# LED-Cube-Schematic.net
KiCad netlist of a schematic drawn in EAGLE
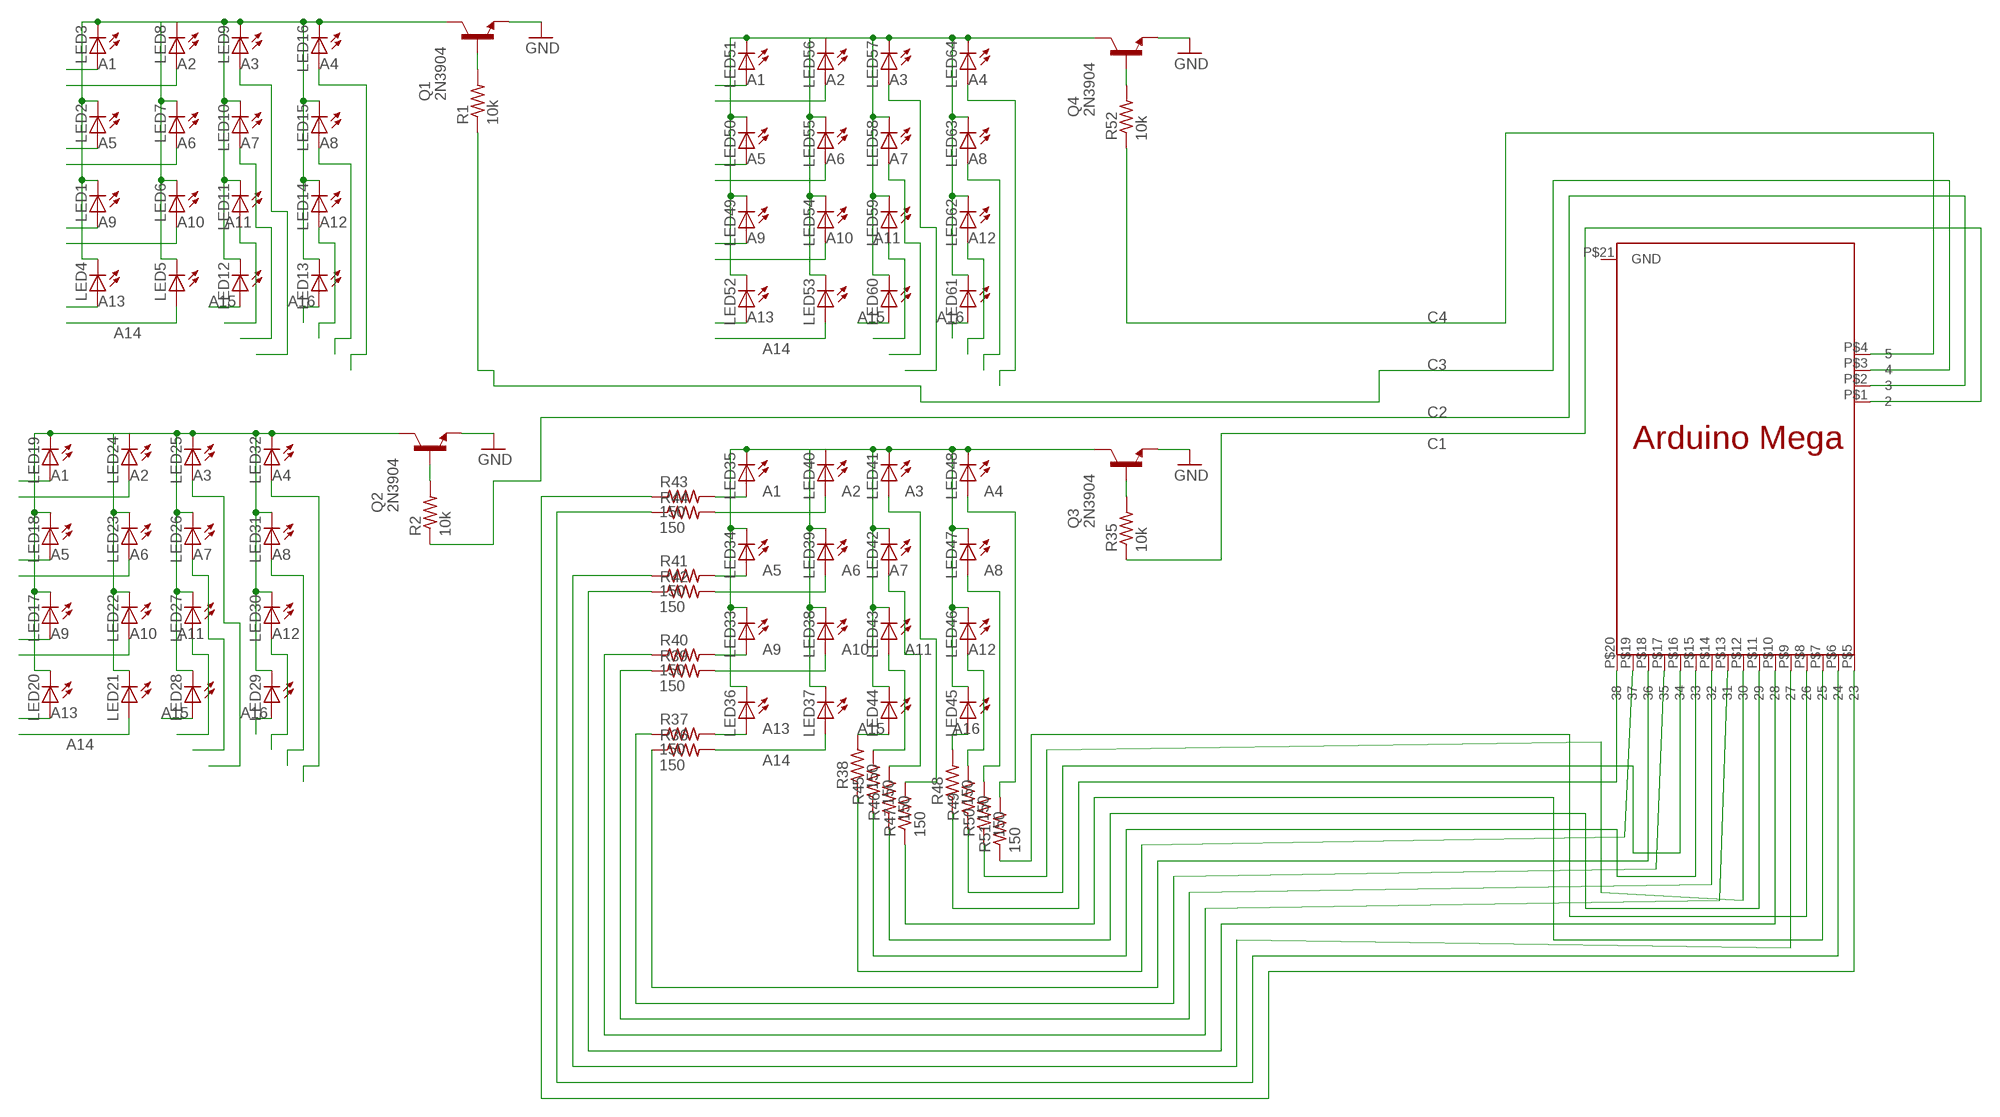
[diagram p0: schematic, sheet 1]

(export (version "E")
  (design (tool "Eeschema 10.0.6"))
  (components
    (comp (ref "LED1")
      (value "LED3MM")
      (footprint "eagle-import:LED3MM")
      (libsource (lib "eagle-import") (part "LED3MM"))
    )
    (comp (ref "LED2")
      (value "LED3MM")
      (footprint "eagle-import:LED3MM")
      (libsource (lib "eagle-import") (part "LED3MM"))
    )
    (comp (ref "LED3")
      (value "LED3MM")
      (footprint "eagle-import:LED3MM")
      (libsource (lib "eagle-import") (part "LED3MM"))
    )
    (comp (ref "LED4")
      (value "LED3MM")
      (footprint "eagle-import:LED3MM")
      (libsource (lib "eagle-import") (part "LED3MM"))
    )
    (comp (ref "LED5")
      (value "LED3MM")
      (footprint "eagle-import:LED3MM")
      (libsource (lib "eagle-import") (part "LED3MM"))
    )
    (comp (ref "LED6")
      (value "LED3MM")
      (footprint "eagle-import:LED3MM")
      (libsource (lib "eagle-import") (part "LED3MM"))
    )
    (comp (ref "LED7")
      (value "LED3MM")
      (footprint "eagle-import:LED3MM")
      (libsource (lib "eagle-import") (part "LED3MM"))
    )
    (comp (ref "LED8")
      (value "LED3MM")
      (footprint "eagle-import:LED3MM")
      (libsource (lib "eagle-import") (part "LED3MM"))
    )
    (comp (ref "LED9")
      (value "LED3MM")
      (footprint "eagle-import:LED3MM")
      (libsource (lib "eagle-import") (part "LED3MM"))
    )
    (comp (ref "LED10")
      (value "LED3MM")
      (footprint "eagle-import:LED3MM")
      (libsource (lib "eagle-import") (part "LED3MM"))
    )
    (comp (ref "LED11")
      (value "LED3MM")
      (footprint "eagle-import:LED3MM")
      (libsource (lib "eagle-import") (part "LED3MM"))
    )
    (comp (ref "LED12")
      (value "LED3MM")
      (footprint "eagle-import:LED3MM")
      (libsource (lib "eagle-import") (part "LED3MM"))
    )
    (comp (ref "LED13")
      (value "LED3MM")
      (footprint "eagle-import:LED3MM")
      (libsource (lib "eagle-import") (part "LED3MM"))
    )
    (comp (ref "LED14")
      (value "LED3MM")
      (footprint "eagle-import:LED3MM")
      (libsource (lib "eagle-import") (part "LED3MM"))
    )
    (comp (ref "LED15")
      (value "LED3MM")
      (footprint "eagle-import:LED3MM")
      (libsource (lib "eagle-import") (part "LED3MM"))
    )
    (comp (ref "LED16")
      (value "LED3MM")
      (footprint "eagle-import:LED3MM")
      (libsource (lib "eagle-import") (part "LED3MM"))
    )
    (comp (ref "LED17")
      (value "LED3MM")
      (footprint "eagle-import:LED3MM")
      (libsource (lib "eagle-import") (part "LED3MM"))
    )
    (comp (ref "LED18")
      (value "LED3MM")
      (footprint "eagle-import:LED3MM")
      (libsource (lib "eagle-import") (part "LED3MM"))
    )
    (comp (ref "LED19")
      (value "LED3MM")
      (footprint "eagle-import:LED3MM")
      (libsource (lib "eagle-import") (part "LED3MM"))
    )
    (comp (ref "LED20")
      (value "LED3MM")
      (footprint "eagle-import:LED3MM")
      (libsource (lib "eagle-import") (part "LED3MM"))
    )
    (comp (ref "LED21")
      (value "LED3MM")
      (footprint "eagle-import:LED3MM")
      (libsource (lib "eagle-import") (part "LED3MM"))
    )
    (comp (ref "LED22")
      (value "LED3MM")
      (footprint "eagle-import:LED3MM")
      (libsource (lib "eagle-import") (part "LED3MM"))
    )
    (comp (ref "LED23")
      (value "LED3MM")
      (footprint "eagle-import:LED3MM")
      (libsource (lib "eagle-import") (part "LED3MM"))
    )
    (comp (ref "LED24")
      (value "LED3MM")
      (footprint "eagle-import:LED3MM")
      (libsource (lib "eagle-import") (part "LED3MM"))
    )
    (comp (ref "LED25")
      (value "LED3MM")
      (footprint "eagle-import:LED3MM")
      (libsource (lib "eagle-import") (part "LED3MM"))
    )
    (comp (ref "LED26")
      (value "LED3MM")
      (footprint "eagle-import:LED3MM")
      (libsource (lib "eagle-import") (part "LED3MM"))
    )
    (comp (ref "LED27")
      (value "LED3MM")
      (footprint "eagle-import:LED3MM")
      (libsource (lib "eagle-import") (part "LED3MM"))
    )
    (comp (ref "LED28")
      (value "LED3MM")
      (footprint "eagle-import:LED3MM")
      (libsource (lib "eagle-import") (part "LED3MM"))
    )
    (comp (ref "LED29")
      (value "LED3MM")
      (footprint "eagle-import:LED3MM")
      (libsource (lib "eagle-import") (part "LED3MM"))
    )
    (comp (ref "LED30")
      (value "LED3MM")
      (footprint "eagle-import:LED3MM")
      (libsource (lib "eagle-import") (part "LED3MM"))
    )
    (comp (ref "LED31")
      (value "LED3MM")
      (footprint "eagle-import:LED3MM")
      (libsource (lib "eagle-import") (part "LED3MM"))
    )
    (comp (ref "LED32")
      (value "LED3MM")
      (footprint "eagle-import:LED3MM")
      (libsource (lib "eagle-import") (part "LED3MM"))
    )
    (comp (ref "LED33")
      (value "LED3MM")
      (footprint "eagle-import:LED3MM")
      (libsource (lib "eagle-import") (part "LED3MM"))
    )
    (comp (ref "LED34")
      (value "LED3MM")
      (footprint "eagle-import:LED3MM")
      (libsource (lib "eagle-import") (part "LED3MM"))
    )
    (comp (ref "LED35")
      (value "LED3MM")
      (footprint "eagle-import:LED3MM")
      (libsource (lib "eagle-import") (part "LED3MM"))
    )
    (comp (ref "LED36")
      (value "LED3MM")
      (footprint "eagle-import:LED3MM")
      (libsource (lib "eagle-import") (part "LED3MM"))
    )
    (comp (ref "LED37")
      (value "LED3MM")
      (footprint "eagle-import:LED3MM")
      (libsource (lib "eagle-import") (part "LED3MM"))
    )
    (comp (ref "LED38")
      (value "LED3MM")
      (footprint "eagle-import:LED3MM")
      (libsource (lib "eagle-import") (part "LED3MM"))
    )
    (comp (ref "LED39")
      (value "LED3MM")
      (footprint "eagle-import:LED3MM")
      (libsource (lib "eagle-import") (part "LED3MM"))
    )
    (comp (ref "LED40")
      (value "LED3MM")
      (footprint "eagle-import:LED3MM")
      (libsource (lib "eagle-import") (part "LED3MM"))
    )
    (comp (ref "LED41")
      (value "LED3MM")
      (footprint "eagle-import:LED3MM")
      (libsource (lib "eagle-import") (part "LED3MM"))
    )
    (comp (ref "LED42")
      (value "LED3MM")
      (footprint "eagle-import:LED3MM")
      (libsource (lib "eagle-import") (part "LED3MM"))
    )
    (comp (ref "LED43")
      (value "LED3MM")
      (footprint "eagle-import:LED3MM")
      (libsource (lib "eagle-import") (part "LED3MM"))
    )
    (comp (ref "LED44")
      (value "LED3MM")
      (footprint "eagle-import:LED3MM")
      (libsource (lib "eagle-import") (part "LED3MM"))
    )
    (comp (ref "LED45")
      (value "LED3MM")
      (footprint "eagle-import:LED3MM")
      (libsource (lib "eagle-import") (part "LED3MM"))
    )
    (comp (ref "LED46")
      (value "LED3MM")
      (footprint "eagle-import:LED3MM")
      (libsource (lib "eagle-import") (part "LED3MM"))
    )
    (comp (ref "LED47")
      (value "LED3MM")
      (footprint "eagle-import:LED3MM")
      (libsource (lib "eagle-import") (part "LED3MM"))
    )
    (comp (ref "LED48")
      (value "LED3MM")
      (footprint "eagle-import:LED3MM")
      (libsource (lib "eagle-import") (part "LED3MM"))
    )
    (comp (ref "LED49")
      (value "LED3MM")
      (footprint "eagle-import:LED3MM")
      (libsource (lib "eagle-import") (part "LED3MM"))
    )
    (comp (ref "LED50")
      (value "LED3MM")
      (footprint "eagle-import:LED3MM")
      (libsource (lib "eagle-import") (part "LED3MM"))
    )
    (comp (ref "LED51")
      (value "LED3MM")
      (footprint "eagle-import:LED3MM")
      (libsource (lib "eagle-import") (part "LED3MM"))
    )
    (comp (ref "LED52")
      (value "LED3MM")
      (footprint "eagle-import:LED3MM")
      (libsource (lib "eagle-import") (part "LED3MM"))
    )
    (comp (ref "LED53")
      (value "LED3MM")
      (footprint "eagle-import:LED3MM")
      (libsource (lib "eagle-import") (part "LED3MM"))
    )
    (comp (ref "LED54")
      (value "LED3MM")
      (footprint "eagle-import:LED3MM")
      (libsource (lib "eagle-import") (part "LED3MM"))
    )
    (comp (ref "LED55")
      (value "LED3MM")
      (footprint "eagle-import:LED3MM")
      (libsource (lib "eagle-import") (part "LED3MM"))
    )
    (comp (ref "LED56")
      (value "LED3MM")
      (footprint "eagle-import:LED3MM")
      (libsource (lib "eagle-import") (part "LED3MM"))
    )
    (comp (ref "LED57")
      (value "LED3MM")
      (footprint "eagle-import:LED3MM")
      (libsource (lib "eagle-import") (part "LED3MM"))
    )
    (comp (ref "LED58")
      (value "LED3MM")
      (footprint "eagle-import:LED3MM")
      (libsource (lib "eagle-import") (part "LED3MM"))
    )
    (comp (ref "LED59")
      (value "LED3MM")
      (footprint "eagle-import:LED3MM")
      (libsource (lib "eagle-import") (part "LED3MM"))
    )
    (comp (ref "LED60")
      (value "LED3MM")
      (footprint "eagle-import:LED3MM")
      (libsource (lib "eagle-import") (part "LED3MM"))
    )
    (comp (ref "LED61")
      (value "LED3MM")
      (footprint "eagle-import:LED3MM")
      (libsource (lib "eagle-import") (part "LED3MM"))
    )
    (comp (ref "LED62")
      (value "LED3MM")
      (footprint "eagle-import:LED3MM")
      (libsource (lib "eagle-import") (part "LED3MM"))
    )
    (comp (ref "LED63")
      (value "LED3MM")
      (footprint "eagle-import:LED3MM")
      (libsource (lib "eagle-import") (part "LED3MM"))
    )
    (comp (ref "LED64")
      (value "LED3MM")
      (footprint "eagle-import:LED3MM")
      (libsource (lib "eagle-import") (part "LED3MM"))
    )
    (comp (ref "Q1")
      (value "2N3904")
      (footprint "eagle-import:TO92")
      (libsource (lib "eagle-import") (part "2N3904"))
    )
    (comp (ref "Q2")
      (value "2N3904")
      (footprint "eagle-import:TO92")
      (libsource (lib "eagle-import") (part "2N3904"))
    )
    (comp (ref "Q3")
      (value "2N3904")
      (footprint "eagle-import:TO92")
      (libsource (lib "eagle-import") (part "2N3904"))
    )
    (comp (ref "Q4")
      (value "2N3904")
      (footprint "eagle-import:TO92")
      (libsource (lib "eagle-import") (part "2N3904"))
    )
    (comp (ref "R1")
      (value "10k")
      (footprint "eagle-import:0207_7")
      (libsource (lib "eagle-import") (part "R-US_0207/7"))
    )
    (comp (ref "R2")
      (value "10k")
      (footprint "eagle-import:0207_7")
      (libsource (lib "eagle-import") (part "R-US_0207/7"))
    )
    (comp (ref "R35")
      (value "10k")
      (footprint "eagle-import:0207_7")
      (libsource (lib "eagle-import") (part "R-US_0207/7"))
    )
    (comp (ref "R36")
      (value "150")
      (footprint "eagle-import:0207_7")
      (libsource (lib "eagle-import") (part "R-US_0207/7"))
    )
    (comp (ref "R37")
      (value "150")
      (footprint "eagle-import:0207_7")
      (libsource (lib "eagle-import") (part "R-US_0207/7"))
    )
    (comp (ref "R38")
      (value "150")
      (footprint "eagle-import:0207_7")
      (libsource (lib "eagle-import") (part "R-US_0207/7"))
    )
    (comp (ref "R39")
      (value "150")
      (footprint "eagle-import:0207_7")
      (libsource (lib "eagle-import") (part "R-US_0207/7"))
    )
    (comp (ref "R40")
      (value "150")
      (footprint "eagle-import:0207_7")
      (libsource (lib "eagle-import") (part "R-US_0207/7"))
    )
    (comp (ref "R41")
      (value "150")
      (footprint "eagle-import:0207_7")
      (libsource (lib "eagle-import") (part "R-US_0207/7"))
    )
    (comp (ref "R42")
      (value "150")
      (footprint "eagle-import:0207_7")
      (libsource (lib "eagle-import") (part "R-US_0207/7"))
    )
    (comp (ref "R43")
      (value "150")
      (footprint "eagle-import:0207_7")
      (libsource (lib "eagle-import") (part "R-US_0207/7"))
    )
    (comp (ref "R44")
      (value "150")
      (footprint "eagle-import:0207_7")
      (libsource (lib "eagle-import") (part "R-US_0207/7"))
    )
    (comp (ref "R45")
      (value "150")
      (footprint "eagle-import:0207_7")
      (libsource (lib "eagle-import") (part "R-US_0207/7"))
    )
    (comp (ref "R46")
      (value "150")
      (footprint "eagle-import:0207_7")
      (libsource (lib "eagle-import") (part "R-US_0207/7"))
    )
    (comp (ref "R47")
      (value "150")
      (footprint "eagle-import:0207_7")
      (libsource (lib "eagle-import") (part "R-US_0207/7"))
    )
    (comp (ref "R48")
      (value "150")
      (footprint "eagle-import:0207_7")
      (libsource (lib "eagle-import") (part "R-US_0207/7"))
    )
    (comp (ref "R49")
      (value "150")
      (footprint "eagle-import:0207_7")
      (libsource (lib "eagle-import") (part "R-US_0207/7"))
    )
    (comp (ref "R50")
      (value "150")
      (footprint "eagle-import:0207_7")
      (libsource (lib "eagle-import") (part "R-US_0207/7"))
    )
    (comp (ref "R51")
      (value "150")
      (footprint "eagle-import:0207_7")
      (libsource (lib "eagle-import") (part "R-US_0207/7"))
    )
    (comp (ref "R52")
      (value "10k")
      (footprint "eagle-import:0207_7")
      (libsource (lib "eagle-import") (part "R-US_0207/7"))
    )
    (comp (ref "U$1")
      (value "MEGA")
      (footprint "eagle-import:MEGAPACKAGE")
      (libsource (lib "eagle-import") (part "MEGA"))
    )
  )
  (nets
    (net (code "1") (name "/A1") (class "Default")
      (node (ref "LED19") (pin "A") (pinfunction "A_A") (pintype "passive"))
      (node (ref "LED3") (pin "A") (pinfunction "A_A") (pintype "passive"))
      (node (ref "LED35") (pin "A") (pinfunction "A_A") (pintype "passive"))
      (node (ref "LED51") (pin "A") (pinfunction "A_A") (pintype "passive"))
      (node (ref "R43") (pin "2") (pinfunction "2_2") (pintype "passive"))
    )
    (net (code "2") (name "/A2") (class "Default")
      (node (ref "LED24") (pin "A") (pinfunction "A_A") (pintype "passive"))
      (node (ref "LED40") (pin "A") (pinfunction "A_A") (pintype "passive"))
      (node (ref "LED56") (pin "A") (pinfunction "A_A") (pintype "passive"))
      (node (ref "LED8") (pin "A") (pinfunction "A_A") (pintype "passive"))
      (node (ref "R44") (pin "2") (pinfunction "2_2") (pintype "passive"))
    )
    (net (code "3") (name "/A3") (class "Default")
      (node (ref "LED25") (pin "A") (pinfunction "A_A") (pintype "passive"))
      (node (ref "LED41") (pin "A") (pinfunction "A_A") (pintype "passive"))
      (node (ref "LED57") (pin "A") (pinfunction "A_A") (pintype "passive"))
      (node (ref "LED9") (pin "A") (pinfunction "A_A") (pintype "passive"))
      (node (ref "R47") (pin "2") (pinfunction "2_2") (pintype "passive"))
    )
    (net (code "4") (name "/A4") (class "Default")
      (node (ref "LED16") (pin "A") (pinfunction "A_A") (pintype "passive"))
      (node (ref "LED32") (pin "A") (pinfunction "A_A") (pintype "passive"))
      (node (ref "LED48") (pin "A") (pinfunction "A_A") (pintype "passive"))
      (node (ref "LED64") (pin "A") (pinfunction "A_A") (pintype "passive"))
      (node (ref "R51") (pin "2") (pinfunction "2_2") (pintype "passive"))
    )
    (net (code "5") (name "/A5") (class "Default")
      (node (ref "LED18") (pin "A") (pinfunction "A_A") (pintype "passive"))
      (node (ref "LED2") (pin "A") (pinfunction "A_A") (pintype "passive"))
      (node (ref "LED34") (pin "A") (pinfunction "A_A") (pintype "passive"))
      (node (ref "LED50") (pin "A") (pinfunction "A_A") (pintype "passive"))
      (node (ref "R41") (pin "2") (pinfunction "2_2") (pintype "passive"))
    )
    (net (code "6") (name "/A6") (class "Default")
      (node (ref "LED23") (pin "A") (pinfunction "A_A") (pintype "passive"))
      (node (ref "LED39") (pin "A") (pinfunction "A_A") (pintype "passive"))
      (node (ref "LED55") (pin "A") (pinfunction "A_A") (pintype "passive"))
      (node (ref "LED7") (pin "A") (pinfunction "A_A") (pintype "passive"))
      (node (ref "R42") (pin "2") (pinfunction "2_2") (pintype "passive"))
    )
    (net (code "7") (name "/A7") (class "Default")
      (node (ref "LED10") (pin "A") (pinfunction "A_A") (pintype "passive"))
      (node (ref "LED26") (pin "A") (pinfunction "A_A") (pintype "passive"))
      (node (ref "LED42") (pin "A") (pinfunction "A_A") (pintype "passive"))
      (node (ref "LED58") (pin "A") (pinfunction "A_A") (pintype "passive"))
      (node (ref "R46") (pin "2") (pinfunction "2_2") (pintype "passive"))
    )
    (net (code "8") (name "/A8") (class "Default")
      (node (ref "LED15") (pin "A") (pinfunction "A_A") (pintype "passive"))
      (node (ref "LED31") (pin "A") (pinfunction "A_A") (pintype "passive"))
      (node (ref "LED47") (pin "A") (pinfunction "A_A") (pintype "passive"))
      (node (ref "LED63") (pin "A") (pinfunction "A_A") (pintype "passive"))
      (node (ref "R50") (pin "2") (pinfunction "2_2") (pintype "passive"))
    )
    (net (code "9") (name "/A9") (class "Default")
      (node (ref "LED1") (pin "A") (pinfunction "A_A") (pintype "passive"))
      (node (ref "LED17") (pin "A") (pinfunction "A_A") (pintype "passive"))
      (node (ref "LED33") (pin "A") (pinfunction "A_A") (pintype "passive"))
      (node (ref "LED49") (pin "A") (pinfunction "A_A") (pintype "passive"))
      (node (ref "R40") (pin "2") (pinfunction "2_2") (pintype "passive"))
    )
    (net (code "10") (name "/A10") (class "Default")
      (node (ref "LED22") (pin "A") (pinfunction "A_A") (pintype "passive"))
      (node (ref "LED38") (pin "A") (pinfunction "A_A") (pintype "passive"))
      (node (ref "LED54") (pin "A") (pinfunction "A_A") (pintype "passive"))
      (node (ref "LED6") (pin "A") (pinfunction "A_A") (pintype "passive"))
      (node (ref "R39") (pin "2") (pinfunction "2_2") (pintype "passive"))
    )
    (net (code "11") (name "/A11") (class "Default")
      (node (ref "LED11") (pin "A") (pinfunction "A_A") (pintype "passive"))
      (node (ref "LED27") (pin "A") (pinfunction "A_A") (pintype "passive"))
      (node (ref "LED43") (pin "A") (pinfunction "A_A") (pintype "passive"))
      (node (ref "LED59") (pin "A") (pinfunction "A_A") (pintype "passive"))
      (node (ref "R45") (pin "2") (pinfunction "2_2") (pintype "passive"))
    )
    (net (code "12") (name "/A12") (class "Default")
      (node (ref "LED14") (pin "A") (pinfunction "A_A") (pintype "passive"))
      (node (ref "LED30") (pin "A") (pinfunction "A_A") (pintype "passive"))
      (node (ref "LED46") (pin "A") (pinfunction "A_A") (pintype "passive"))
      (node (ref "LED62") (pin "A") (pinfunction "A_A") (pintype "passive"))
      (node (ref "R49") (pin "2") (pinfunction "2_2") (pintype "passive"))
    )
    (net (code "13") (name "/A13") (class "Default")
      (node (ref "LED20") (pin "A") (pinfunction "A_A") (pintype "passive"))
      (node (ref "LED36") (pin "A") (pinfunction "A_A") (pintype "passive"))
      (node (ref "LED4") (pin "A") (pinfunction "A_A") (pintype "passive"))
      (node (ref "LED52") (pin "A") (pinfunction "A_A") (pintype "passive"))
      (node (ref "R37") (pin "2") (pinfunction "2_2") (pintype "passive"))
    )
    (net (code "14") (name "/A14") (class "Default")
      (node (ref "LED21") (pin "A") (pinfunction "A_A") (pintype "passive"))
      (node (ref "LED37") (pin "A") (pinfunction "A_A") (pintype "passive"))
      (node (ref "LED5") (pin "A") (pinfunction "A_A") (pintype "passive"))
      (node (ref "LED53") (pin "A") (pinfunction "A_A") (pintype "passive"))
      (node (ref "R36") (pin "2") (pinfunction "2_2") (pintype "passive"))
    )
    (net (code "15") (name "/A15") (class "Default")
      (node (ref "LED12") (pin "A") (pinfunction "A_A") (pintype "passive"))
      (node (ref "LED28") (pin "A") (pinfunction "A_A") (pintype "passive"))
      (node (ref "LED44") (pin "A") (pinfunction "A_A") (pintype "passive"))
      (node (ref "LED60") (pin "A") (pinfunction "A_A") (pintype "passive"))
      (node (ref "R38") (pin "2") (pinfunction "2_2") (pintype "passive"))
    )
    (net (code "16") (name "/A16") (class "Default")
      (node (ref "LED13") (pin "A") (pinfunction "A_A") (pintype "passive"))
      (node (ref "LED29") (pin "A") (pinfunction "A_A") (pintype "passive"))
      (node (ref "LED45") (pin "A") (pinfunction "A_A") (pintype "passive"))
      (node (ref "LED61") (pin "A") (pinfunction "A_A") (pintype "passive"))
      (node (ref "R48") (pin "2") (pinfunction "2_2") (pintype "passive"))
    )
    (net (code "17") (name "/C1") (class "Default")
      (node (ref "R35") (pin "1") (pinfunction "1_1") (pintype "passive"))
    )
    (net (code "18") (name "/C2") (class "Default")
      (node (ref "R2") (pin "1") (pinfunction "1_1") (pintype "passive"))
    )
    (net (code "19") (name "/C3") (class "Default")
      (node (ref "R1") (pin "1") (pinfunction "1_1") (pintype "passive"))
    )
    (net (code "20") (name "/C4") (class "Default")
      (node (ref "R52") (pin "1") (pinfunction "1_1") (pintype "passive"))
    )
    (net (code "21") (name "GND") (class "Default")
      (node (ref "Q1") (pin "3") (pinfunction "E_3") (pintype "passive"))
      (node (ref "Q2") (pin "3") (pinfunction "E_3") (pintype "passive"))
      (node (ref "Q3") (pin "3") (pinfunction "E_3") (pintype "passive"))
      (node (ref "Q4") (pin "3") (pinfunction "E_3") (pintype "passive"))
    )
    (net (code "22") (name "Net-(LED1-C)") (class "Default")
      (node (ref "LED1") (pin "K") (pinfunction "C_K") (pintype "passive"))
      (node (ref "LED10") (pin "K") (pinfunction "C_K") (pintype "passive"))
      (node (ref "LED11") (pin "K") (pinfunction "C_K") (pintype "passive"))
      (node (ref "LED12") (pin "K") (pinfunction "C_K") (pintype "passive"))
      (node (ref "LED13") (pin "K") (pinfunction "C_K") (pintype "passive"))
      (node (ref "LED14") (pin "K") (pinfunction "C_K") (pintype "passive"))
      (node (ref "LED15") (pin "K") (pinfunction "C_K") (pintype "passive"))
      (node (ref "LED16") (pin "K") (pinfunction "C_K") (pintype "passive"))
      (node (ref "LED2") (pin "K") (pinfunction "C_K") (pintype "passive"))
      (node (ref "LED3") (pin "K") (pinfunction "C_K") (pintype "passive"))
      (node (ref "LED4") (pin "K") (pinfunction "C_K") (pintype "passive"))
      (node (ref "LED9") (pin "K") (pinfunction "C_K") (pintype "passive"))
      (node (ref "Q1") (pin "1") (pinfunction "C_1") (pintype "passive"))
    )
    (net (code "23") (name "Net-(LED5-C)") (class "Default")
      (node (ref "LED5") (pin "K") (pinfunction "C_K") (pintype "passive"))
      (node (ref "LED6") (pin "K") (pinfunction "C_K") (pintype "passive"))
      (node (ref "LED7") (pin "K") (pinfunction "C_K") (pintype "passive"))
      (node (ref "LED8") (pin "K") (pinfunction "C_K") (pintype "passive"))
    )
    (net (code "24") (name "Net-(LED17-C)") (class "Default")
      (node (ref "LED17") (pin "K") (pinfunction "C_K") (pintype "passive"))
      (node (ref "LED18") (pin "K") (pinfunction "C_K") (pintype "passive"))
      (node (ref "LED19") (pin "K") (pinfunction "C_K") (pintype "passive"))
      (node (ref "LED20") (pin "K") (pinfunction "C_K") (pintype "passive"))
      (node (ref "LED25") (pin "K") (pinfunction "C_K") (pintype "passive"))
      (node (ref "LED26") (pin "K") (pinfunction "C_K") (pintype "passive"))
      (node (ref "LED27") (pin "K") (pinfunction "C_K") (pintype "passive"))
      (node (ref "LED28") (pin "K") (pinfunction "C_K") (pintype "passive"))
      (node (ref "LED29") (pin "K") (pinfunction "C_K") (pintype "passive"))
      (node (ref "LED30") (pin "K") (pinfunction "C_K") (pintype "passive"))
      (node (ref "LED31") (pin "K") (pinfunction "C_K") (pintype "passive"))
      (node (ref "LED32") (pin "K") (pinfunction "C_K") (pintype "passive"))
      (node (ref "Q2") (pin "1") (pinfunction "C_1") (pintype "passive"))
    )
    (net (code "25") (name "Net-(LED21-C)") (class "Default")
      (node (ref "LED21") (pin "K") (pinfunction "C_K") (pintype "passive"))
      (node (ref "LED22") (pin "K") (pinfunction "C_K") (pintype "passive"))
      (node (ref "LED23") (pin "K") (pinfunction "C_K") (pintype "passive"))
      (node (ref "LED24") (pin "K") (pinfunction "C_K") (pintype "passive"))
    )
    (net (code "26") (name "Net-(LED33-C)") (class "Default")
      (node (ref "LED33") (pin "K") (pinfunction "C_K") (pintype "passive"))
      (node (ref "LED34") (pin "K") (pinfunction "C_K") (pintype "passive"))
      (node (ref "LED35") (pin "K") (pinfunction "C_K") (pintype "passive"))
      (node (ref "LED36") (pin "K") (pinfunction "C_K") (pintype "passive"))
      (node (ref "LED41") (pin "K") (pinfunction "C_K") (pintype "passive"))
      (node (ref "LED42") (pin "K") (pinfunction "C_K") (pintype "passive"))
      (node (ref "LED43") (pin "K") (pinfunction "C_K") (pintype "passive"))
      (node (ref "LED44") (pin "K") (pinfunction "C_K") (pintype "passive"))
      (node (ref "LED45") (pin "K") (pinfunction "C_K") (pintype "passive"))
      (node (ref "LED46") (pin "K") (pinfunction "C_K") (pintype "passive"))
      (node (ref "LED47") (pin "K") (pinfunction "C_K") (pintype "passive"))
      (node (ref "LED48") (pin "K") (pinfunction "C_K") (pintype "passive"))
      (node (ref "Q3") (pin "1") (pinfunction "C_1") (pintype "passive"))
    )
    (net (code "27") (name "Net-(LED37-C)") (class "Default")
      (node (ref "LED37") (pin "K") (pinfunction "C_K") (pintype "passive"))
      (node (ref "LED38") (pin "K") (pinfunction "C_K") (pintype "passive"))
      (node (ref "LED39") (pin "K") (pinfunction "C_K") (pintype "passive"))
      (node (ref "LED40") (pin "K") (pinfunction "C_K") (pintype "passive"))
    )
    (net (code "28") (name "Net-(LED49-C)") (class "Default")
      (node (ref "LED49") (pin "K") (pinfunction "C_K") (pintype "passive"))
      (node (ref "LED50") (pin "K") (pinfunction "C_K") (pintype "passive"))
      (node (ref "LED51") (pin "K") (pinfunction "C_K") (pintype "passive"))
      (node (ref "LED52") (pin "K") (pinfunction "C_K") (pintype "passive"))
      (node (ref "LED57") (pin "K") (pinfunction "C_K") (pintype "passive"))
      (node (ref "LED58") (pin "K") (pinfunction "C_K") (pintype "passive"))
      (node (ref "LED59") (pin "K") (pinfunction "C_K") (pintype "passive"))
      (node (ref "LED60") (pin "K") (pinfunction "C_K") (pintype "passive"))
      (node (ref "LED61") (pin "K") (pinfunction "C_K") (pintype "passive"))
      (node (ref "LED62") (pin "K") (pinfunction "C_K") (pintype "passive"))
      (node (ref "LED63") (pin "K") (pinfunction "C_K") (pintype "passive"))
      (node (ref "LED64") (pin "K") (pinfunction "C_K") (pintype "passive"))
      (node (ref "Q4") (pin "1") (pinfunction "C_1") (pintype "passive"))
    )
    (net (code "29") (name "Net-(LED53-C)") (class "Default")
      (node (ref "LED53") (pin "K") (pinfunction "C_K") (pintype "passive"))
      (node (ref "LED54") (pin "K") (pinfunction "C_K") (pintype "passive"))
      (node (ref "LED55") (pin "K") (pinfunction "C_K") (pintype "passive"))
      (node (ref "LED56") (pin "K") (pinfunction "C_K") (pintype "passive"))
    )
    (net (code "30") (name "Net-(Q1-B)") (class "Default")
      (node (ref "Q1") (pin "2") (pinfunction "B_2") (pintype "passive"))
      (node (ref "R1") (pin "2") (pinfunction "2_2") (pintype "passive"))
    )
    (net (code "31") (name "Net-(Q2-B)") (class "Default")
      (node (ref "Q2") (pin "2") (pinfunction "B_2") (pintype "passive"))
      (node (ref "R2") (pin "2") (pinfunction "2_2") (pintype "passive"))
    )
    (net (code "32") (name "Net-(Q3-B)") (class "Default")
      (node (ref "Q3") (pin "2") (pinfunction "B_2") (pintype "passive"))
      (node (ref "R35") (pin "2") (pinfunction "2_2") (pintype "passive"))
    )
    (net (code "33") (name "Net-(Q4-B)") (class "Default")
      (node (ref "Q4") (pin "2") (pinfunction "B_2") (pintype "passive"))
      (node (ref "R52") (pin "2") (pinfunction "2_2") (pintype "passive"))
    )
    (net (code "34") (name "unconnected-(R36-Pad1)") (class "Default")
      (node (ref "R36") (pin "1") (pinfunction "1_1") (pintype "passive"))
    )
    (net (code "35") (name "unconnected-(R37-Pad1)") (class "Default")
      (node (ref "R37") (pin "1") (pinfunction "1_1") (pintype "passive"))
    )
    (net (code "36") (name "unconnected-(R38-Pad1)") (class "Default")
      (node (ref "R38") (pin "1") (pinfunction "1_1") (pintype "passive"))
    )
    (net (code "37") (name "unconnected-(R39-Pad1)") (class "Default")
      (node (ref "R39") (pin "1") (pinfunction "1_1") (pintype "passive"))
    )
    (net (code "38") (name "unconnected-(R40-Pad1)") (class "Default")
      (node (ref "R40") (pin "1") (pinfunction "1_1") (pintype "passive"))
    )
    (net (code "39") (name "unconnected-(R41-Pad1)") (class "Default")
      (node (ref "R41") (pin "1") (pinfunction "1_1") (pintype "passive"))
    )
    (net (code "40") (name "unconnected-(R42-Pad1)") (class "Default")
      (node (ref "R42") (pin "1") (pinfunction "1_1") (pintype "passive"))
    )
    (net (code "41") (name "unconnected-(R43-Pad1)") (class "Default")
      (node (ref "R43") (pin "1") (pinfunction "1_1") (pintype "passive"))
    )
    (net (code "42") (name "unconnected-(R44-Pad1)") (class "Default")
      (node (ref "R44") (pin "1") (pinfunction "1_1") (pintype "passive"))
    )
    (net (code "43") (name "unconnected-(R45-Pad1)") (class "Default")
      (node (ref "R45") (pin "1") (pinfunction "1_1") (pintype "passive"))
    )
    (net (code "44") (name "unconnected-(R46-Pad1)") (class "Default")
      (node (ref "R46") (pin "1") (pinfunction "1_1") (pintype "passive"))
    )
    (net (code "45") (name "unconnected-(R47-Pad1)") (class "Default")
      (node (ref "R47") (pin "1") (pinfunction "1_1") (pintype "passive"))
    )
    (net (code "46") (name "unconnected-(R48-Pad1)") (class "Default")
      (node (ref "R48") (pin "1") (pinfunction "1_1") (pintype "passive"))
    )
    (net (code "47") (name "unconnected-(R49-Pad1)") (class "Default")
      (node (ref "R49") (pin "1") (pinfunction "1_1") (pintype "passive"))
    )
    (net (code "48") (name "unconnected-(R50-Pad1)") (class "Default")
      (node (ref "R50") (pin "1") (pinfunction "1_1") (pintype "passive"))
    )
    (net (code "49") (name "unconnected-(R51-Pad1)") (class "Default")
      (node (ref "R51") (pin "1") (pinfunction "1_1") (pintype "passive"))
    )
    (net (code "50") (name "unconnected-(U$1-2-PadP$1)") (class "Default")
      (node (ref "U$1") (pin "P$1") (pinfunction "2_P$1") (pintype "bidirectional"))
    )
    (net (code "51") (name "unconnected-(U$1-3-PadP$2)") (class "Default")
      (node (ref "U$1") (pin "P$2") (pinfunction "3_P$2") (pintype "bidirectional"))
    )
    (net (code "52") (name "unconnected-(U$1-4-PadP$3)") (class "Default")
      (node (ref "U$1") (pin "P$3") (pinfunction "4_P$3") (pintype "bidirectional"))
    )
    (net (code "53") (name "unconnected-(U$1-5-PadP$4)") (class "Default")
      (node (ref "U$1") (pin "P$4") (pinfunction "5_P$4") (pintype "bidirectional"))
    )
    (net (code "54") (name "unconnected-(U$1-23-PadP$5)") (class "Default")
      (node (ref "U$1") (pin "P$5") (pinfunction "23_P$5") (pintype "bidirectional"))
    )
    (net (code "55") (name "unconnected-(U$1-24-PadP$6)") (class "Default")
      (node (ref "U$1") (pin "P$6") (pinfunction "24_P$6") (pintype "bidirectional"))
    )
    (net (code "56") (name "unconnected-(U$1-25-PadP$7)") (class "Default")
      (node (ref "U$1") (pin "P$7") (pinfunction "25_P$7") (pintype "bidirectional"))
    )
    (net (code "57") (name "unconnected-(U$1-26-PadP$8)") (class "Default")
      (node (ref "U$1") (pin "P$8") (pinfunction "26_P$8") (pintype "bidirectional"))
    )
    (net (code "58") (name "unconnected-(U$1-27-PadP$9)") (class "Default")
      (node (ref "U$1") (pin "P$9") (pinfunction "27_P$9") (pintype "bidirectional"))
    )
    (net (code "59") (name "unconnected-(U$1-28-PadP$10)") (class "Default")
      (node (ref "U$1") (pin "P$10") (pinfunction "28_P$10") (pintype "bidirectional"))
    )
    (net (code "60") (name "unconnected-(U$1-29-PadP$11)") (class "Default")
      (node (ref "U$1") (pin "P$11") (pinfunction "29_P$11") (pintype "bidirectional"))
    )
    (net (code "61") (name "unconnected-(U$1-30-PadP$12)") (class "Default")
      (node (ref "U$1") (pin "P$12") (pinfunction "30_P$12") (pintype "bidirectional"))
    )
    (net (code "62") (name "unconnected-(U$1-31-PadP$13)") (class "Default")
      (node (ref "U$1") (pin "P$13") (pinfunction "31_P$13") (pintype "bidirectional"))
    )
    (net (code "63") (name "unconnected-(U$1-32-PadP$14)") (class "Default")
      (node (ref "U$1") (pin "P$14") (pinfunction "32_P$14") (pintype "bidirectional"))
    )
    (net (code "64") (name "unconnected-(U$1-33-PadP$15)") (class "Default")
      (node (ref "U$1") (pin "P$15") (pinfunction "33_P$15") (pintype "bidirectional"))
    )
    (net (code "65") (name "unconnected-(U$1-34-PadP$16)") (class "Default")
      (node (ref "U$1") (pin "P$16") (pinfunction "34_P$16") (pintype "bidirectional"))
    )
    (net (code "66") (name "unconnected-(U$1-35-PadP$17)") (class "Default")
      (node (ref "U$1") (pin "P$17") (pinfunction "35_P$17") (pintype "bidirectional"))
    )
    (net (code "67") (name "unconnected-(U$1-36-PadP$18)") (class "Default")
      (node (ref "U$1") (pin "P$18") (pinfunction "36_P$18") (pintype "bidirectional"))
    )
    (net (code "68") (name "unconnected-(U$1-37-PadP$19)") (class "Default")
      (node (ref "U$1") (pin "P$19") (pinfunction "37_P$19") (pintype "bidirectional"))
    )
    (net (code "69") (name "unconnected-(U$1-38-PadP$20)") (class "Default")
      (node (ref "U$1") (pin "P$20") (pinfunction "38_P$20") (pintype "bidirectional"))
    )
    (net (code "70") (name "unconnected-(U$1-GND-PadP$21)") (class "Default")
      (node (ref "U$1") (pin "P$21") (pinfunction "GND_P$21") (pintype "bidirectional"))
    )
  )
)
